# DC_DC_5V_2.net
KiCad netlist of a schematic drawn in Altium Designer
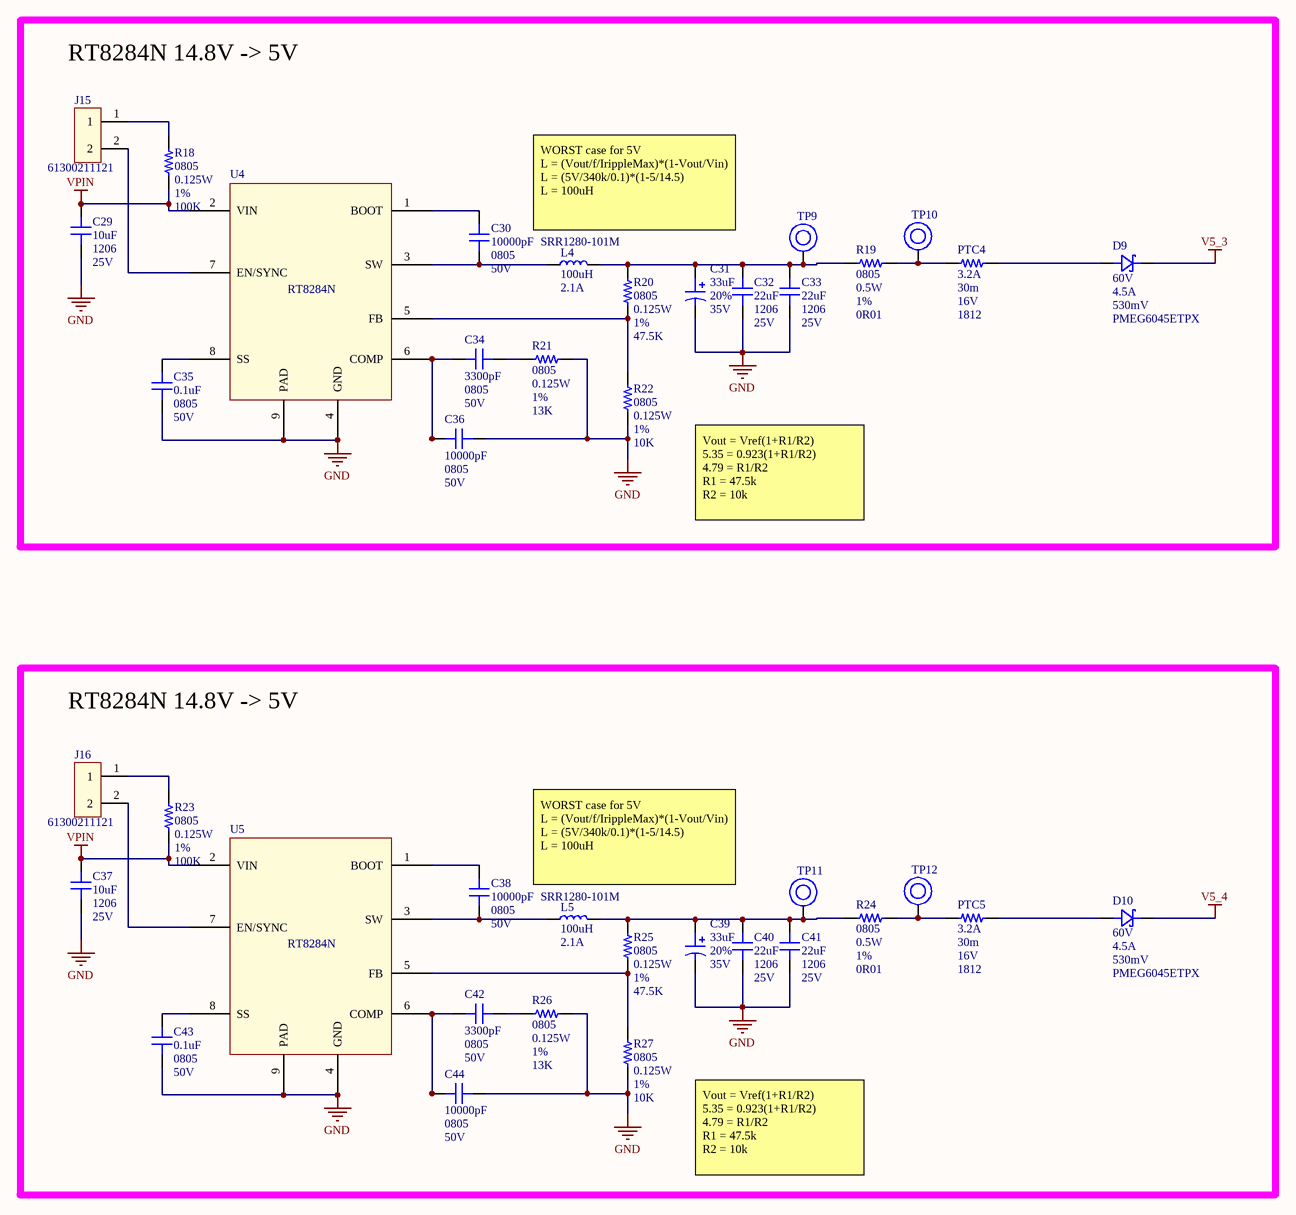
[diagram p0: DC_DC_5V_2.SchDoc]

(export (version "E")
  (design (tool "Eeschema 10.0.6"))
  (components
    (comp (ref "C29")
      (value "10uF")
      (footprint "CAP_1206")
      (description "CAP CER 10uF 25V 1206")
      (fields
        (field (name "PART NUMBER") "CL31A106KAHNFNE‎")
        (field (name "PACKAGE") "1206")
        (field (name "VOLTAGE") "25V")
        (field (name "Comment") "CAP_‎CL31A106KAHNFNE‎")
      )
      (libsource (lib "SecureBot") (part "CAP_‎CL31A106KAHNFNE‎"))
    )
    (comp (ref "C30")
      (value "10000pF")
      (footprint "CAP_0805")
      (description "CAP CER 10000pF 50V 0805")
      (fields
        (field (name "PART NUMBER") "‎CL21B103KBANNNC")
        (field (name "PACKAGE") "0805")
        (field (name "VOLTAGE") "50V")
        (field (name "Comment") "CAP_‎‎‎‎CL21B103KBANNNC")
      )
      (libsource (lib "SecureBot") (part "CAP_‎‎‎‎CL21B103KBANNNC"))
    )
    (comp (ref "C31")
      (value "33uF")
      (footprint "CAP ALU - 6.3mm DIA")
      (description "CAP ALU 33µF 35V")
      (fields
        (field (name "PART NUMBER") "EEE-FK1V330P")
        (field (name "TOLERANCE") "20%")
        (field (name "VOLTAGE") "35V")
        (field (name "Comment") "CAP_EEE-FK1V330P")
      )
      (libsource (lib "SecureBot") (part "CAP_EEE-FK1V330P"))
    )
    (comp (ref "C32")
      (value "22uF")
      (footprint "CAP_1206")
      (description "CAP CER 22uF 25V 1206")
      (fields
        (field (name "PART NUMBER") "CL31A226KAHNNNE‎")
        (field (name "PACKAGE") "1206")
        (field (name "VOLTAGE") "25V")
        (field (name "Comment") "CAP_‎‎CL31A226KAHNNNE‎")
      )
      (libsource (lib "SecureBot") (part "CAP_‎‎CL31A226KAHNNNE‎"))
    )
    (comp (ref "C33")
      (value "22uF")
      (footprint "CAP_1206")
      (description "CAP CER 22uF 25V 1206")
      (fields
        (field (name "PART NUMBER") "CL31A226KAHNNNE‎")
        (field (name "PACKAGE") "1206")
        (field (name "VOLTAGE") "25V")
        (field (name "Comment") "CAP_‎‎CL31A226KAHNNNE‎")
      )
      (libsource (lib "SecureBot") (part "CAP_‎‎CL31A226KAHNNNE‎"))
    )
    (comp (ref "C34")
      (value "3300pF")
      (footprint "CAP_0805")
      (description "CAP CER 3300pF 50V 0805")
      (fields
        (field (name "PART NUMBER") "CL21B332KBANNNC‎")
        (field (name "PACKAGE") "0805")
        (field (name "VOLTAGE") "50V")
        (field (name "Comment") "CAP_CL21B332KBANNNC‎")
      )
      (libsource (lib "SecureBot") (part "CAP_CL21B332KBANNNC‎"))
    )
    (comp (ref "C35")
      (value "0.1uF")
      (footprint "CAP_0805")
      (description "CAP CER 0.1uF 50V 0805")
      (fields
        (field (name "PART NUMBER") "CC0805KRX7R9BB104‎")
        (field (name "PACKAGE") "0805")
        (field (name "VOLTAGE") "50V")
        (field (name "Comment") "CAP_CC0805KRX7R9BB104‎")
      )
      (libsource (lib "SecureBot") (part "CAP_CC0805KRX7R9BB104‎"))
    )
    (comp (ref "C36")
      (value "10000pF")
      (footprint "CAP_0805")
      (description "CAP CER 10000pF 50V 0805")
      (fields
        (field (name "PART NUMBER") "‎CL21B103KBANNNC")
        (field (name "PACKAGE") "0805")
        (field (name "VOLTAGE") "50V")
        (field (name "Comment") "CAP_‎‎‎‎CL21B103KBANNNC")
      )
      (libsource (lib "SecureBot") (part "CAP_‎‎‎‎CL21B103KBANNNC"))
    )
    (comp (ref "C37")
      (value "10uF")
      (footprint "CAP_1206")
      (description "CAP CER 10uF 25V 1206")
      (fields
        (field (name "PART NUMBER") "CL31A106KAHNFNE‎")
        (field (name "PACKAGE") "1206")
        (field (name "VOLTAGE") "25V")
        (field (name "Comment") "CAP_‎CL31A106KAHNFNE‎")
      )
      (libsource (lib "SecureBot") (part "CAP_‎CL31A106KAHNFNE‎"))
    )
    (comp (ref "C38")
      (value "10000pF")
      (footprint "CAP_0805")
      (description "CAP CER 10000pF 50V 0805")
      (fields
        (field (name "PART NUMBER") "‎CL21B103KBANNNC")
        (field (name "PACKAGE") "0805")
        (field (name "VOLTAGE") "50V")
        (field (name "Comment") "CAP_‎‎‎‎CL21B103KBANNNC")
      )
      (libsource (lib "SecureBot") (part "CAP_‎‎‎‎CL21B103KBANNNC"))
    )
    (comp (ref "C39")
      (value "33uF")
      (footprint "CAP ALU - 6.3mm DIA")
      (description "CAP ALU 33µF 35V")
      (fields
        (field (name "PART NUMBER") "EEE-FK1V330P")
        (field (name "TOLERANCE") "20%")
        (field (name "VOLTAGE") "35V")
        (field (name "Comment") "CAP_EEE-FK1V330P")
      )
      (libsource (lib "SecureBot") (part "CAP_EEE-FK1V330P"))
    )
    (comp (ref "C40")
      (value "22uF")
      (footprint "CAP_1206")
      (description "CAP CER 22uF 25V 1206")
      (fields
        (field (name "PART NUMBER") "CL31A226KAHNNNE‎")
        (field (name "PACKAGE") "1206")
        (field (name "VOLTAGE") "25V")
        (field (name "Comment") "CAP_‎‎CL31A226KAHNNNE‎")
      )
      (libsource (lib "SecureBot") (part "CAP_‎‎CL31A226KAHNNNE‎"))
    )
    (comp (ref "C41")
      (value "22uF")
      (footprint "CAP_1206")
      (description "CAP CER 22uF 25V 1206")
      (fields
        (field (name "PART NUMBER") "CL31A226KAHNNNE‎")
        (field (name "PACKAGE") "1206")
        (field (name "VOLTAGE") "25V")
        (field (name "Comment") "CAP_‎‎CL31A226KAHNNNE‎")
      )
      (libsource (lib "SecureBot") (part "CAP_‎‎CL31A226KAHNNNE‎"))
    )
    (comp (ref "C42")
      (value "3300pF")
      (footprint "CAP_0805")
      (description "CAP CER 3300pF 50V 0805")
      (fields
        (field (name "PART NUMBER") "CL21B332KBANNNC‎")
        (field (name "PACKAGE") "0805")
        (field (name "VOLTAGE") "50V")
        (field (name "Comment") "CAP_CL21B332KBANNNC‎")
      )
      (libsource (lib "SecureBot") (part "CAP_CL21B332KBANNNC‎"))
    )
    (comp (ref "C43")
      (value "0.1uF")
      (footprint "CAP_0805")
      (description "CAP CER 0.1uF 50V 0805")
      (fields
        (field (name "PART NUMBER") "CC0805KRX7R9BB104‎")
        (field (name "PACKAGE") "0805")
        (field (name "VOLTAGE") "50V")
        (field (name "Comment") "CAP_CC0805KRX7R9BB104‎")
      )
      (libsource (lib "SecureBot") (part "CAP_CC0805KRX7R9BB104‎"))
    )
    (comp (ref "C44")
      (value "10000pF")
      (footprint "CAP_0805")
      (description "CAP CER 10000pF 50V 0805")
      (fields
        (field (name "PART NUMBER") "‎CL21B103KBANNNC")
        (field (name "PACKAGE") "0805")
        (field (name "VOLTAGE") "50V")
        (field (name "Comment") "CAP_‎‎‎‎CL21B103KBANNNC")
      )
      (libsource (lib "SecureBot") (part "CAP_‎‎‎‎CL21B103KBANNNC"))
    )
    (comp (ref "D9")
      (value "DIODE_SCH_PMEG6045ETPX")
      (footprint "DO-214AC_SOD128")
      (description "Diode Schottky 60V 4.5A Surface Mount CFP5")
      (fields
        (field (name "VOLTAGE") "60V")
        (field (name "CURRENT") "4.5A")
        (field (name "VF") "530mV")
        (field (name "PART NUMBER") "PMEG6045ETPX")
      )
      (libsource (lib "SecureBot") (part "DIODE_SCH_PMEG6045ETPX"))
    )
    (comp (ref "D10")
      (value "DIODE_SCH_PMEG6045ETPX")
      (footprint "DO-214AC_SOD128")
      (description "Diode Schottky 60V 4.5A Surface Mount CFP5")
      (fields
        (field (name "VOLTAGE") "60V")
        (field (name "CURRENT") "4.5A")
        (field (name "VF") "530mV")
        (field (name "PART NUMBER") "PMEG6045ETPX")
      )
      (libsource (lib "SecureBot") (part "DIODE_SCH_PMEG6045ETPX"))
    )
    (comp (ref "J15")
      (value "Header 2 pin SM")
      (footprint "HDR1X2")
      (fields (field (name "PART NUMBER") "61300211121"))
      (libsource (lib "SecureBot") (part "Header 2 pin SM"))
    )
    (comp (ref "J16")
      (value "Header 2 pin SM")
      (footprint "HDR1X2")
      (fields (field (name "PART NUMBER") "61300211121"))
      (libsource (lib "SecureBot") (part "Header 2 pin SM"))
    )
    (comp (ref "L4")
      (value "100uH")
      (footprint "BOURNS 12.5x12.5mm")
      (description "IND 100µH Shielded Wirewound Inductor 2.1A")
      (fields
        (field (name "TOLERANCE") "20%")
        (field (name "CURRENT") "2.1A")
        (field (name "PART NUMBER") "SRR1280-101M")
        (field (name "Comment") "IND_SRR1280-101M")
      )
      (libsource (lib "SecureBot") (part "IND_SRR1280-101M"))
    )
    (comp (ref "L5")
      (value "100uH")
      (footprint "BOURNS 12.5x12.5mm")
      (description "IND 100µH Shielded Wirewound Inductor 2.1A")
      (fields
        (field (name "TOLERANCE") "20%")
        (field (name "CURRENT") "2.1A")
        (field (name "PART NUMBER") "SRR1280-101M")
        (field (name "Comment") "IND_SRR1280-101M")
      )
      (libsource (lib "SecureBot") (part "IND_SRR1280-101M"))
    )
    (comp (ref "PTC4")
      (value "PTC_0ZCG0160BF2C")
      (footprint "PTC - 1812")
      (description "PTC_Polymeric PTC Resettable Fuse 16V 1.6A Ih")
      (fields
        (field (name "PART NUMBER") "0ZCG0160BF2C")
        (field (name "TRIP VALUE") "3.2A")
        (field (name "RES") "30m")
        (field (name "VOLTAGE") "16V")
        (field (name "PACKAGE") "1812")
      )
      (libsource (lib "SecureBot") (part "PTC_0ZCG0160BF2C"))
    )
    (comp (ref "PTC5")
      (value "PTC_0ZCG0160BF2C")
      (footprint "PTC - 1812")
      (description "PTC_Polymeric PTC Resettable Fuse 16V 1.6A Ih")
      (fields
        (field (name "PART NUMBER") "0ZCG0160BF2C")
        (field (name "TRIP VALUE") "3.2A")
        (field (name "RES") "30m")
        (field (name "VOLTAGE") "16V")
        (field (name "PACKAGE") "1812")
      )
      (libsource (lib "SecureBot") (part "PTC_0ZCG0160BF2C"))
    )
    (comp (ref "R18")
      (value "100K")
      (footprint "RES_0805")
      (description "RES 100K 1% 1/8W 0805")
      (fields
        (field (name "PART NUMBER") "‎RMCF0805FT100K‎")
        (field (name "PACKAGE") "0805")
        (field (name "POWER") "0.125W")
        (field (name "TOLERANCE") "1%")
        (field (name "Comment") "RES_‎RMCF0805FT100K‎")
      )
      (libsource (lib "SecureBot") (part "RES_‎RMCF0805FT100K‎"))
    )
    (comp (ref "R19")
      (value "0R01")
      (footprint "RES_0805")
      (description "RES 0.01R 1% 1/2W 0805")
      (fields
        (field (name "PART NUMBER") "KRL1220E-M-R010-F-T5")
        (field (name "PACKAGE") "0805")
        (field (name "POWER") "0.5W")
        (field (name "TOLERANCE") "1%")
        (field (name "Comment") "RES_‎‎‎‎‎ KRL1220E-M-R010-F-T5")
      )
      (libsource (lib "SecureBot") (part "RES_‎‎‎‎‎ KRL1220E-M-R010-F-T5"))
    )
    (comp (ref "R20")
      (value "47.5K")
      (footprint "RES_0805")
      (description "RES 47.5K 1% 1/8W 0805")
      (fields
        (field (name "PART NUMBER") "RMCF0805FT47K5‎")
        (field (name "PACKAGE") "0805")
        (field (name "POWER") "0.125W")
        (field (name "TOLERANCE") "1%")
        (field (name "Comment") "RES_‎‎RMCF0805FT47K5‎")
      )
      (libsource (lib "SecureBot") (part "RES_‎‎RMCF0805FT47K5‎"))
    )
    (comp (ref "R21")
      (value "13K")
      (footprint "RES_0805")
      (description "RES 13K 1% 1/8W 0805")
      (fields
        (field (name "PART NUMBER") "RC0805FR-0713KL")
        (field (name "PACKAGE") "0805")
        (field (name "POWER") "0.125W")
        (field (name "TOLERANCE") "1%")
        (field (name "Comment") "RES_‎ RC0805FR-0713KL")
      )
      (libsource (lib "SecureBot") (part "RES_‎ RC0805FR-0713KL"))
    )
    (comp (ref "R22")
      (value "10K")
      (footprint "RES_0805")
      (description "RES 10K 1% 1/8W 0805")
      (fields
        (field (name "PART NUMBER") "RMCF0805FT10K0")
        (field (name "PACKAGE") "0805")
        (field (name "POWER") "0.125W")
        (field (name "TOLERANCE") "1%")
        (field (name "Comment") "RES_‎RMCF0805FT10K0")
      )
      (libsource (lib "SecureBot") (part "RES_‎RMCF0805FT10K0"))
    )
    (comp (ref "R23")
      (value "100K")
      (footprint "RES_0805")
      (description "RES 100K 1% 1/8W 0805")
      (fields
        (field (name "PART NUMBER") "‎RMCF0805FT100K‎")
        (field (name "PACKAGE") "0805")
        (field (name "POWER") "0.125W")
        (field (name "TOLERANCE") "1%")
        (field (name "Comment") "RES_‎RMCF0805FT100K‎")
      )
      (libsource (lib "SecureBot") (part "RES_‎RMCF0805FT100K‎"))
    )
    (comp (ref "R24")
      (value "0R01")
      (footprint "RES_0805")
      (description "RES 0.01R 1% 1/2W 0805")
      (fields
        (field (name "PART NUMBER") "KRL1220E-M-R010-F-T5")
        (field (name "PACKAGE") "0805")
        (field (name "POWER") "0.5W")
        (field (name "TOLERANCE") "1%")
        (field (name "Comment") "RES_‎‎‎‎‎ KRL1220E-M-R010-F-T5")
      )
      (libsource (lib "SecureBot") (part "RES_‎‎‎‎‎ KRL1220E-M-R010-F-T5"))
    )
    (comp (ref "R25")
      (value "47.5K")
      (footprint "RES_0805")
      (description "RES 47.5K 1% 1/8W 0805")
      (fields
        (field (name "PART NUMBER") "RMCF0805FT47K5‎")
        (field (name "PACKAGE") "0805")
        (field (name "POWER") "0.125W")
        (field (name "TOLERANCE") "1%")
        (field (name "Comment") "RES_‎‎RMCF0805FT47K5‎")
      )
      (libsource (lib "SecureBot") (part "RES_‎‎RMCF0805FT47K5‎"))
    )
    (comp (ref "R26")
      (value "13K")
      (footprint "RES_0805")
      (description "RES 13K 1% 1/8W 0805")
      (fields
        (field (name "PART NUMBER") "RC0805FR-0713KL")
        (field (name "PACKAGE") "0805")
        (field (name "POWER") "0.125W")
        (field (name "TOLERANCE") "1%")
        (field (name "Comment") "RES_‎ RC0805FR-0713KL")
      )
      (libsource (lib "SecureBot") (part "RES_‎ RC0805FR-0713KL"))
    )
    (comp (ref "R27")
      (value "10K")
      (footprint "RES_0805")
      (description "RES 10K 1% 1/8W 0805")
      (fields
        (field (name "PART NUMBER") "RMCF0805FT10K0")
        (field (name "PACKAGE") "0805")
        (field (name "POWER") "0.125W")
        (field (name "TOLERANCE") "1%")
        (field (name "Comment") "RES_‎RMCF0805FT10K0")
      )
      (libsource (lib "SecureBot") (part "RES_‎RMCF0805FT10K0"))
    )
    (comp (ref "TP9")
      (value "TestPoint 3x3mm")
      (footprint "TestPoint 3X3mm")
      (libsource (lib "SecureBot") (part "TestPoint 3x3mm"))
    )
    (comp (ref "TP10")
      (value "TestPoint 3x3mm")
      (footprint "TestPoint 3X3mm")
      (libsource (lib "SecureBot") (part "TestPoint 3x3mm"))
    )
    (comp (ref "TP11")
      (value "TestPoint 3x3mm")
      (footprint "TestPoint 3X3mm")
      (libsource (lib "SecureBot") (part "TestPoint 3x3mm"))
    )
    (comp (ref "TP12")
      (value "TestPoint 3x3mm")
      (footprint "TestPoint 3X3mm")
      (libsource (lib "SecureBot") (part "TestPoint 3x3mm"))
    )
    (comp (ref "U4")
      (value "REG_SW_RT8284N")
      (footprint "SOP8")
      (description "REG 2A, 23V, 340kHz Synchronous Step-Down Converter")
      (fields (field (name "PART NUMBER") "RT8284N"))
      (libsource (lib "SecureBot") (part "REG_SW_RT8284N"))
    )
    (comp (ref "U5")
      (value "REG_SW_RT8284N")
      (footprint "SOP8")
      (description "REG 2A, 23V, 340kHz Synchronous Step-Down Converter")
      (fields (field (name "PART NUMBER") "RT8284N"))
      (libsource (lib "SecureBot") (part "REG_SW_RT8284N"))
    )
  )
  (nets
    (net (code "1") (name "GND") (class "Default")
      (node (ref "C29") (pin "2") (pinfunction "2_2") (pintype "passive"))
      (node (ref "C31") (pin "2") (pinfunction "2_2") (pintype "passive"))
      (node (ref "C32") (pin "2") (pinfunction "2_2") (pintype "passive"))
      (node (ref "C33") (pin "2") (pinfunction "2_2") (pintype "passive"))
      (node (ref "C35") (pin "2") (pinfunction "2_2") (pintype "passive"))
      (node (ref "C36") (pin "2") (pinfunction "2_2") (pintype "passive"))
      (node (ref "C37") (pin "2") (pinfunction "2_2") (pintype "passive"))
      (node (ref "C39") (pin "2") (pinfunction "2_2") (pintype "passive"))
      (node (ref "C40") (pin "2") (pinfunction "2_2") (pintype "passive"))
      (node (ref "C41") (pin "2") (pinfunction "2_2") (pintype "passive"))
      (node (ref "C43") (pin "2") (pinfunction "2_2") (pintype "passive"))
      (node (ref "C44") (pin "2") (pinfunction "2_2") (pintype "passive"))
      (node (ref "R21") (pin "2") (pinfunction "2_2") (pintype "passive"))
      (node (ref "R22") (pin "2") (pinfunction "2_2") (pintype "passive"))
      (node (ref "R26") (pin "2") (pinfunction "2_2") (pintype "passive"))
      (node (ref "R27") (pin "2") (pinfunction "2_2") (pintype "passive"))
      (node (ref "U4") (pin "4") (pinfunction "GND_4") (pintype "passive"))
      (node (ref "U4") (pin "9") (pinfunction "PAD_9") (pintype "passive"))
      (node (ref "U5") (pin "4") (pinfunction "GND_4") (pintype "passive"))
      (node (ref "U5") (pin "9") (pinfunction "PAD_9") (pintype "passive"))
    )
    (net (code "2") (name "Net-(C31-Pad1)") (class "Default")
      (node (ref "C31") (pin "1") (pinfunction "1_1") (pintype "passive"))
      (node (ref "C32") (pin "1") (pinfunction "1_1") (pintype "passive"))
      (node (ref "C33") (pin "1") (pinfunction "1_1") (pintype "passive"))
      (node (ref "L4") (pin "2") (pinfunction "2_2") (pintype "passive"))
      (node (ref "R19") (pin "1") (pinfunction "1_1") (pintype "passive"))
      (node (ref "R20") (pin "1") (pinfunction "1_1") (pintype "passive"))
      (node (ref "TP9") (pin "1") (pinfunction "1_1") (pintype "passive"))
    )
    (net (code "3") (name "Net-(C34-Pad2)") (class "Default")
      (node (ref "C34") (pin "2") (pinfunction "2_2") (pintype "passive"))
      (node (ref "R21") (pin "1") (pinfunction "1_1") (pintype "passive"))
    )
    (net (code "4") (name "Net-(C39-Pad1)") (class "Default")
      (node (ref "C39") (pin "1") (pinfunction "1_1") (pintype "passive"))
      (node (ref "C40") (pin "1") (pinfunction "1_1") (pintype "passive"))
      (node (ref "C41") (pin "1") (pinfunction "1_1") (pintype "passive"))
      (node (ref "L5") (pin "2") (pinfunction "2_2") (pintype "passive"))
      (node (ref "R24") (pin "1") (pinfunction "1_1") (pintype "passive"))
      (node (ref "R25") (pin "1") (pinfunction "1_1") (pintype "passive"))
      (node (ref "TP11") (pin "1") (pinfunction "1_1") (pintype "passive"))
    )
    (net (code "5") (name "Net-(C42-Pad2)") (class "Default")
      (node (ref "C42") (pin "2") (pinfunction "2_2") (pintype "passive"))
      (node (ref "R26") (pin "1") (pinfunction "1_1") (pintype "passive"))
    )
    (net (code "6") (name "Net-(D9-Pad1)") (class "Default")
      (node (ref "D9") (pin "1") (pinfunction "1_1") (pintype "passive"))
      (node (ref "PTC4") (pin "2") (pinfunction "2_2") (pintype "passive"))
    )
    (net (code "7") (name "Net-(D10-Pad1)") (class "Default")
      (node (ref "D10") (pin "1") (pinfunction "1_1") (pintype "passive"))
      (node (ref "PTC5") (pin "2") (pinfunction "2_2") (pintype "passive"))
    )
    (net (code "8") (name "Net-(J15-Pad1)") (class "Default")
      (node (ref "J15") (pin "1") (pinfunction "1_1") (pintype "passive"))
      (node (ref "R18") (pin "2") (pinfunction "2_2") (pintype "passive"))
    )
    (net (code "9") (name "Net-(J16-Pad1)") (class "Default")
      (node (ref "J16") (pin "1") (pinfunction "1_1") (pintype "passive"))
      (node (ref "R23") (pin "2") (pinfunction "2_2") (pintype "passive"))
    )
    (net (code "10") (name "Net-(PTC4-Pad1)") (class "Default")
      (node (ref "PTC4") (pin "1") (pinfunction "1_1") (pintype "passive"))
      (node (ref "R19") (pin "2") (pinfunction "2_2") (pintype "passive"))
      (node (ref "TP10") (pin "1") (pinfunction "1_1") (pintype "passive"))
    )
    (net (code "11") (name "Net-(PTC5-Pad1)") (class "Default")
      (node (ref "PTC5") (pin "1") (pinfunction "1_1") (pintype "passive"))
      (node (ref "R24") (pin "2") (pinfunction "2_2") (pintype "passive"))
      (node (ref "TP12") (pin "1") (pinfunction "1_1") (pintype "passive"))
    )
    (net (code "12") (name "Net-(U4-BOOT)") (class "Default")
      (node (ref "C30") (pin "1") (pinfunction "1_1") (pintype "passive"))
      (node (ref "U4") (pin "1") (pinfunction "BOOT_1") (pintype "passive"))
    )
    (net (code "13") (name "Net-(U4-COMP)") (class "Default")
      (node (ref "C34") (pin "1") (pinfunction "1_1") (pintype "passive"))
      (node (ref "C36") (pin "1") (pinfunction "1_1") (pintype "passive"))
      (node (ref "U4") (pin "6") (pinfunction "COMP_6") (pintype "passive"))
    )
    (net (code "14") (name "Net-(U4-EN{slash}SYNC)") (class "Default")
      (node (ref "J15") (pin "2") (pinfunction "2_2") (pintype "passive"))
      (node (ref "U4") (pin "7") (pinfunction "EN/SYNC_7") (pintype "passive"))
    )
    (net (code "15") (name "Net-(U4-FB)") (class "Default")
      (node (ref "R20") (pin "2") (pinfunction "2_2") (pintype "passive"))
      (node (ref "R22") (pin "1") (pinfunction "1_1") (pintype "passive"))
      (node (ref "U4") (pin "5") (pinfunction "FB_5") (pintype "passive"))
    )
    (net (code "16") (name "Net-(U4-SS)") (class "Default")
      (node (ref "C35") (pin "1") (pinfunction "1_1") (pintype "passive"))
      (node (ref "U4") (pin "8") (pinfunction "SS_8") (pintype "passive"))
    )
    (net (code "17") (name "Net-(U4-SW)") (class "Default")
      (node (ref "C30") (pin "2") (pinfunction "2_2") (pintype "passive"))
      (node (ref "L4") (pin "1") (pinfunction "1_1") (pintype "passive"))
      (node (ref "U4") (pin "3") (pinfunction "SW_3") (pintype "passive"))
    )
    (net (code "18") (name "Net-(U5-BOOT)") (class "Default")
      (node (ref "C38") (pin "1") (pinfunction "1_1") (pintype "passive"))
      (node (ref "U5") (pin "1") (pinfunction "BOOT_1") (pintype "passive"))
    )
    (net (code "19") (name "Net-(U5-COMP)") (class "Default")
      (node (ref "C42") (pin "1") (pinfunction "1_1") (pintype "passive"))
      (node (ref "C44") (pin "1") (pinfunction "1_1") (pintype "passive"))
      (node (ref "U5") (pin "6") (pinfunction "COMP_6") (pintype "passive"))
    )
    (net (code "20") (name "Net-(U5-EN{slash}SYNC)") (class "Default")
      (node (ref "J16") (pin "2") (pinfunction "2_2") (pintype "passive"))
      (node (ref "U5") (pin "7") (pinfunction "EN/SYNC_7") (pintype "passive"))
    )
    (net (code "21") (name "Net-(U5-FB)") (class "Default")
      (node (ref "R25") (pin "2") (pinfunction "2_2") (pintype "passive"))
      (node (ref "R27") (pin "1") (pinfunction "1_1") (pintype "passive"))
      (node (ref "U5") (pin "5") (pinfunction "FB_5") (pintype "passive"))
    )
    (net (code "22") (name "Net-(U5-SS)") (class "Default")
      (node (ref "C43") (pin "1") (pinfunction "1_1") (pintype "passive"))
      (node (ref "U5") (pin "8") (pinfunction "SS_8") (pintype "passive"))
    )
    (net (code "23") (name "Net-(U5-SW)") (class "Default")
      (node (ref "C38") (pin "2") (pinfunction "2_2") (pintype "passive"))
      (node (ref "L5") (pin "1") (pinfunction "1_1") (pintype "passive"))
      (node (ref "U5") (pin "3") (pinfunction "SW_3") (pintype "passive"))
    )
    (net (code "24") (name "V5_3") (class "Default")
      (node (ref "D9") (pin "2") (pinfunction "2_2") (pintype "passive"))
    )
    (net (code "25") (name "V5_4") (class "Default")
      (node (ref "D10") (pin "2") (pinfunction "2_2") (pintype "passive"))
    )
    (net (code "26") (name "VPIN") (class "Default")
      (node (ref "C29") (pin "1") (pinfunction "1_1") (pintype "passive"))
      (node (ref "C37") (pin "1") (pinfunction "1_1") (pintype "passive"))
      (node (ref "R18") (pin "1") (pinfunction "1_1") (pintype "passive"))
      (node (ref "R23") (pin "1") (pinfunction "1_1") (pintype "passive"))
      (node (ref "U4") (pin "2") (pinfunction "VIN_2") (pintype "passive"))
      (node (ref "U5") (pin "2") (pinfunction "VIN_2") (pintype "passive"))
    )
  )
)
